# Stick_SD_Serayu_2024.net
KiCad netlist of a schematic drawn in EAGLE
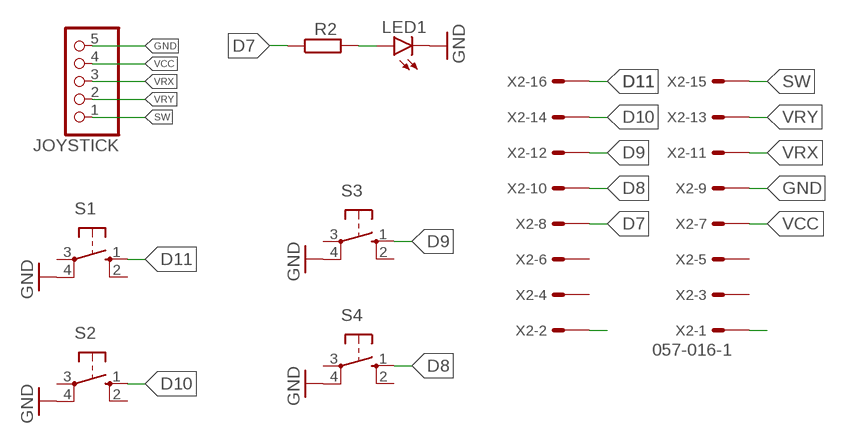
[diagram p0: schematic, sheet 1]

(export (version "E")
  (design (tool "Eeschema 10.0.6"))
  (components
    (comp (ref "JOYSTICK")
      (value "PINHD-1X5")
      (footprint "eagle-import:1X05")
      (libsource (lib "eagle-import") (part "PINHD-1X5"))
    )
    (comp (ref "LED1")
      (value "LED5MM")
      (footprint "eagle-import:LED5MM")
      (libsource (lib "eagle-import") (part "LED5MM"))
    )
    (comp (ref "R2")
      (value "R-EU_R1206")
      (footprint "eagle-import:R1206")
      (libsource (lib "eagle-import") (part "R-EU_R1206"))
    )
    (comp (ref "S1")
      (value "40-XX")
      (footprint "eagle-import:B3F-40XX")
      (fields (field (name "MF") "OMRON COMPONENTS USA") (field (name "MPN") "B3F-4000"))
      (libsource (lib "eagle-import") (part "40-XX"))
    )
    (comp (ref "S2")
      (value "40-XX")
      (footprint "eagle-import:B3F-40XX")
      (fields (field (name "MF") "OMRON COMPONENTS USA") (field (name "MPN") "B3F-4000"))
      (libsource (lib "eagle-import") (part "40-XX"))
    )
    (comp (ref "S3")
      (value "40-XX")
      (footprint "eagle-import:B3F-40XX")
      (fields (field (name "MF") "OMRON COMPONENTS USA") (field (name "MPN") "B3F-4000"))
      (libsource (lib "eagle-import") (part "40-XX"))
    )
    (comp (ref "S4")
      (value "40-XX")
      (footprint "eagle-import:B3F-40XX")
      (fields (field (name "MF") "OMRON COMPONENTS USA") (field (name "MPN") "B3F-4000"))
      (libsource (lib "eagle-import") (part "40-XX"))
    )
    (comp (ref "X2")
      (value "057-016-1")
      (footprint "eagle-import:057-016-1")
      (libsource (lib "eagle-import") (part "057-016-1"))
    )
  )
  (nets
    (net (code "1") (name "D7") (class "Default")
      (node (ref "R2") (pin "1") (pinfunction "1_1") (pintype "passive"))
      (node (ref "X2") (pin "8") (pinfunction "S_8") (pintype "passive"))
    )
    (net (code "2") (name "D8") (class "Default")
      (node (ref "S4") (pin "1") (pinfunction "S_1") (pintype "passive"))
      (node (ref "X2") (pin "10") (pinfunction "S_10") (pintype "passive"))
    )
    (net (code "3") (name "D9") (class "Default")
      (node (ref "S3") (pin "1") (pinfunction "S_1") (pintype "passive"))
      (node (ref "X2") (pin "12") (pinfunction "S_12") (pintype "passive"))
    )
    (net (code "4") (name "D10") (class "Default")
      (node (ref "S2") (pin "1") (pinfunction "S_1") (pintype "passive"))
      (node (ref "X2") (pin "14") (pinfunction "S_14") (pintype "passive"))
    )
    (net (code "5") (name "D11") (class "Default")
      (node (ref "S1") (pin "1") (pinfunction "S_1") (pintype "passive"))
      (node (ref "X2") (pin "16") (pinfunction "S_16") (pintype "passive"))
    )
    (net (code "6") (name "GND") (class "Default")
      (node (ref "JOYSTICK") (pin "5") (pinfunction "5_5") (pintype "passive"))
      (node (ref "LED1") (pin "K") (pinfunction "C_K") (pintype "passive"))
      (node (ref "S1") (pin "4") (pinfunction "P1_4") (pintype "passive"))
      (node (ref "S2") (pin "4") (pinfunction "P1_4") (pintype "passive"))
      (node (ref "S3") (pin "4") (pinfunction "P1_4") (pintype "passive"))
      (node (ref "S4") (pin "4") (pinfunction "P1_4") (pintype "passive"))
      (node (ref "X2") (pin "9") (pinfunction "S_9") (pintype "passive"))
    )
    (net (code "7") (name "Net-(LED1-PadA)") (class "Default")
      (node (ref "LED1") (pin "A") (pinfunction "A_A") (pintype "passive"))
      (node (ref "R2") (pin "2") (pinfunction "2_2") (pintype "passive"))
    )
    (net (code "8") (name "SW") (class "Default")
      (node (ref "JOYSTICK") (pin "1") (pinfunction "1_1") (pintype "passive"))
      (node (ref "X2") (pin "15") (pinfunction "S_15") (pintype "passive"))
    )
    (net (code "9") (name "VCC") (class "Default")
      (node (ref "JOYSTICK") (pin "4") (pinfunction "4_4") (pintype "passive"))
      (node (ref "X2") (pin "7") (pinfunction "S_7") (pintype "passive"))
    )
    (net (code "10") (name "VRX") (class "Default")
      (node (ref "JOYSTICK") (pin "3") (pinfunction "3_3") (pintype "passive"))
      (node (ref "X2") (pin "11") (pinfunction "S_11") (pintype "passive"))
    )
    (net (code "11") (name "VRY") (class "Default")
      (node (ref "JOYSTICK") (pin "2") (pinfunction "2_2") (pintype "passive"))
      (node (ref "X2") (pin "13") (pinfunction "S_13") (pintype "passive"))
    )
    (net (code "12") (name "unconnected-(S1-P-Pad3)") (class "Default")
      (node (ref "S1") (pin "3") (pinfunction "P_3") (pintype "passive"))
    )
    (net (code "13") (name "unconnected-(S1-S1-Pad2)") (class "Default")
      (node (ref "S1") (pin "2") (pinfunction "S1_2") (pintype "passive"))
    )
    (net (code "14") (name "unconnected-(S2-P-Pad3)") (class "Default")
      (node (ref "S2") (pin "3") (pinfunction "P_3") (pintype "passive"))
    )
    (net (code "15") (name "unconnected-(S2-S1-Pad2)") (class "Default")
      (node (ref "S2") (pin "2") (pinfunction "S1_2") (pintype "passive"))
    )
    (net (code "16") (name "unconnected-(S3-P-Pad3)") (class "Default")
      (node (ref "S3") (pin "3") (pinfunction "P_3") (pintype "passive"))
    )
    (net (code "17") (name "unconnected-(S3-S1-Pad2)") (class "Default")
      (node (ref "S3") (pin "2") (pinfunction "S1_2") (pintype "passive"))
    )
    (net (code "18") (name "unconnected-(S4-P-Pad3)") (class "Default")
      (node (ref "S4") (pin "3") (pinfunction "P_3") (pintype "passive"))
    )
    (net (code "19") (name "unconnected-(S4-S1-Pad2)") (class "Default")
      (node (ref "S4") (pin "2") (pinfunction "S1_2") (pintype "passive"))
    )
    (net (code "20") (name "unconnected-(X2A-S-Pad1)") (class "Default")
      (node (ref "X2") (pin "1") (pinfunction "S_1") (pintype "passive"))
    )
    (net (code "21") (name "unconnected-(X2I-S-Pad2)") (class "Default")
      (node (ref "X2") (pin "2") (pinfunction "S_2") (pintype "passive"))
    )
    (net (code "22") (name "unconnected-(X2J-S-Pad3)") (class "Default")
      (node (ref "X2") (pin "3") (pinfunction "S_3") (pintype "passive"))
    )
    (net (code "23") (name "unconnected-(X2K-S-Pad4)") (class "Default")
      (node (ref "X2") (pin "4") (pinfunction "S_4") (pintype "passive"))
    )
    (net (code "24") (name "unconnected-(X2L-S-Pad5)") (class "Default")
      (node (ref "X2") (pin "5") (pinfunction "S_5") (pintype "passive"))
    )
    (net (code "25") (name "unconnected-(X2M-S-Pad6)") (class "Default")
      (node (ref "X2") (pin "6") (pinfunction "S_6") (pintype "passive"))
    )
  )
)
